# PWR_P3V3.net
KiCad netlist of a schematic drawn in Altium Designer
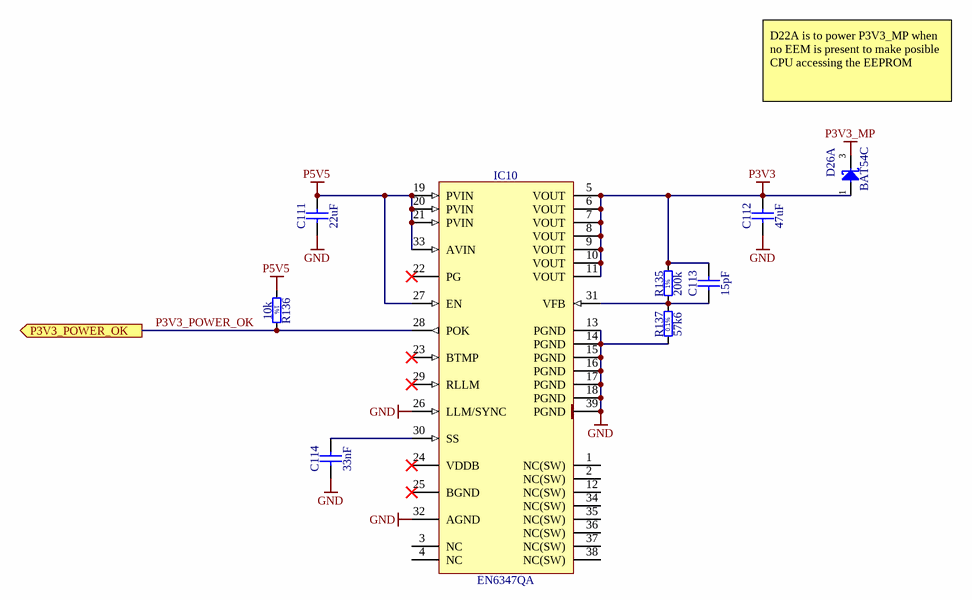
[diagram p0: PWR_P3V3.SchDoc]

(export (version "E")
  (design (tool "Eeschema 10.0.6"))
  (components
    (comp (ref "C111")
      (value "22uF")
      (footprint "CAPC2012X135N")
      (description "Non-polarised capacitor")
      (fields
        (field (name "PART NUMBER") "CC0805_22UF_16V_10%_X5R")
        (field (name "VOLTAGE") "16V")
        (field (name "AUTHOR") "CERN DEM JLC")
      )
      (libsource (lib "Capacitors") (part "Capacitor - non polarized"))
    )
    (comp (ref "C112")
      (value "47uF")
      (footprint "CAPC3216X180N")
      (description "Non-polarised capacitor")
      (fields
        (field (name "PART NUMBER") "CC1206_47UF_25V_20%_X5R")
        (field (name "VOLTAGE") "25V")
        (field (name "AUTHOR") "CERN DEM JLC")
      )
      (libsource (lib "Capacitors") (part "Capacitor - non polarized"))
    )
    (comp (ref "C113")
      (value "15pF")
      (footprint "CAPC1005X55N")
      (description "Non-polarised capacitor")
      (fields
        (field (name "PART NUMBER") "CC0402_15PF_50V_5%_C0G")
        (field (name "VOLTAGE") "50V")
        (field (name "AUTHOR") "CERN DEM JLC")
      )
      (libsource (lib "Capacitors") (part "Capacitor - non polarized"))
    )
    (comp (ref "C114")
      (value "33nF")
      (footprint "CAPC1005X55N")
      (description "Non-polarised capacitor")
      (fields
        (field (name "PART NUMBER") "CC0402_33NF_16V_10%_X7R")
        (field (name "VOLTAGE") "16V")
        (field (name "AUTHOR") "CERN DEM JLC")
      )
      (libsource (lib "Capacitors") (part "Capacitor - non polarized"))
    )
    (comp (ref "D26")
      (value "BAT54C")
      (footprint "SOT95P240X130-3N")
      (description "Dual Common Cathode Schottky Diodes")
      (fields
        (field (name "VOLTAGE") "30V")
        (field (name "POWER") "200mA")
        (field (name "AUTHOR") "CERN DEM JLC")
      )
      (libsource (lib "ICs And Semiconductors") (part "Diode Schottky x2 A1C3_A2C3"))
    )
    (comp (ref "IC10")
      (value "EN6347QA")
      (footprint "EN63xx")
      (description "4A PowerSoC Voltage Mode Synchronous PWM Buck with Integrated Inductor")
      (libsource (lib "altium-import") (part "root_0_EN6347QA_"))
    )
    (comp (ref "R135")
      (value "200k")
      (footprint "RESC1005X40N")
      (description "Resistor - 1%")
      (fields
        (field (name "PART NUMBER") "R0402_200K_1%_0.0625W_100PPM")
        (field (name "MANUFACTURER") "GENERIC")
        (field (name "AUTHOR") "CERN DEM JLC")
      )
      (libsource (lib "Resistors") (part "Resistor - 1%"))
    )
    (comp (ref "R136")
      (value "10k")
      (footprint "RESC1005X40N")
      (description "Resistor - 1%")
      (fields
        (field (name "PART NUMBER") "R0402_10K_1%_0.0625W_100PPM")
        (field (name "MANUFACTURER") "GENERIC")
        (field (name "AUTHOR") "CERN DEM JLC")
      )
      (libsource (lib "Resistors") (part "Resistor - 1%"))
    )
    (comp (ref "R137")
      (value "57k6")
      (footprint "RESC1608X55N")
      (description "Resistor - 0.1%")
      (fields
        (field (name "PART NUMBER") "R0603_57K6_0.1%_0.063W_10PPM")
        (field (name "MANUFACTURER") "GENERIC")
        (field (name "AUTHOR") "CERN DEM JLC")
      )
      (libsource (lib "Resistors") (part "Resistor - 0.1%"))
    )
  )
  (nets
    (net (code "1") (name "/P3V3_POWER_OK") (class "Default")
      (node (ref "IC10") (pin "28") (pinfunction "POK_28") (pintype "output"))
      (node (ref "R136") (pin "2") (pinfunction "2_2") (pintype "passive"))
    )
    (net (code "2") (name "GND") (class "Default")
      (node (ref "C111") (pin "1") (pinfunction "1_1") (pintype "passive"))
      (node (ref "C112") (pin "1") (pinfunction "1_1") (pintype "passive"))
      (node (ref "C114") (pin "1") (pinfunction "1_1") (pintype "passive"))
      (node (ref "IC10") (pin "13") (pinfunction "PGND_13") (pintype "power_in"))
      (node (ref "IC10") (pin "14") (pinfunction "PGND_14") (pintype "power_in"))
      (node (ref "IC10") (pin "15") (pinfunction "PGND_15") (pintype "power_in"))
      (node (ref "IC10") (pin "16") (pinfunction "PGND_16") (pintype "power_in"))
      (node (ref "IC10") (pin "17") (pinfunction "PGND_17") (pintype "power_in"))
      (node (ref "IC10") (pin "18") (pinfunction "PGND_18") (pintype "power_in"))
      (node (ref "IC10") (pin "26") (pinfunction "LLM/SYNC_26") (pintype "input"))
      (node (ref "IC10") (pin "32") (pinfunction "AGND_32") (pintype "power_in"))
      (node (ref "IC10") (pin "39") (pinfunction "PGND_39") (pintype "power_in"))
      (node (ref "R137") (pin "1") (pinfunction "1_1") (pintype "passive"))
    )
    (net (code "3") (name "Net-(IC10-SS)") (class "Default")
      (node (ref "C114") (pin "2") (pinfunction "2_2") (pintype "passive"))
      (node (ref "IC10") (pin "30") (pinfunction "SS_30") (pintype "input"))
    )
    (net (code "4") (name "Net-(IC10-VFB)") (class "Default")
      (node (ref "C113") (pin "1") (pinfunction "1_1") (pintype "passive"))
      (node (ref "IC10") (pin "31") (pinfunction "VFB_31") (pintype "input"))
      (node (ref "R135") (pin "1") (pinfunction "1_1") (pintype "passive"))
      (node (ref "R137") (pin "2") (pinfunction "2_2") (pintype "passive"))
    )
    (net (code "5") (name "P3V3") (class "Default")
      (node (ref "C112") (pin "2") (pinfunction "2_2") (pintype "passive"))
      (node (ref "C113") (pin "2") (pinfunction "2_2") (pintype "passive"))
      (node (ref "D26") (pin "1") (pinfunction "A_1") (pintype "passive"))
      (node (ref "IC10") (pin "10") (pinfunction "VOUT_10") (pintype "power_in"))
      (node (ref "IC10") (pin "11") (pinfunction "VOUT_11") (pintype "power_in"))
      (node (ref "IC10") (pin "5") (pinfunction "VOUT_5") (pintype "power_in"))
      (node (ref "IC10") (pin "6") (pinfunction "VOUT_6") (pintype "power_in"))
      (node (ref "IC10") (pin "7") (pinfunction "VOUT_7") (pintype "power_in"))
      (node (ref "IC10") (pin "8") (pinfunction "VOUT_8") (pintype "power_in"))
      (node (ref "IC10") (pin "9") (pinfunction "VOUT_9") (pintype "power_in"))
      (node (ref "R135") (pin "2") (pinfunction "2_2") (pintype "passive"))
    )
    (net (code "6") (name "P3V3_MP") (class "Default")
      (node (ref "D26") (pin "3") (pinfunction "COMC_3") (pintype "passive"))
    )
    (net (code "7") (name "P5V5") (class "Default")
      (node (ref "C111") (pin "2") (pinfunction "2_2") (pintype "passive"))
      (node (ref "IC10") (pin "19") (pinfunction "PVIN_19") (pintype "input"))
      (node (ref "IC10") (pin "20") (pinfunction "PVIN_20") (pintype "input"))
      (node (ref "IC10") (pin "21") (pinfunction "PVIN_21") (pintype "input"))
      (node (ref "IC10") (pin "27") (pinfunction "EN_27") (pintype "input"))
      (node (ref "IC10") (pin "33") (pinfunction "AVIN_33") (pintype "input"))
      (node (ref "R136") (pin "1") (pinfunction "1_1") (pintype "passive"))
    )
    (net (code "8") (name "unconnected-(IC10-BGND-Pad25)") (class "Default")
      (node (ref "IC10") (pin "25") (pinfunction "BGND_25") (pintype "power_in+no_connect"))
    )
    (net (code "9") (name "unconnected-(IC10-BTMP-Pad23)") (class "Default")
      (node (ref "IC10") (pin "23") (pinfunction "BTMP_23") (pintype "input+no_connect"))
    )
    (net (code "10") (name "unconnected-(IC10-NC(SW)-Pad1)") (class "Default")
      (node (ref "IC10") (pin "1") (pinfunction "NC(SW)_1") (pintype "passive"))
    )
    (net (code "11") (name "unconnected-(IC10-NC(SW)-Pad2)") (class "Default")
      (node (ref "IC10") (pin "2") (pinfunction "NC(SW)_2") (pintype "passive"))
    )
    (net (code "12") (name "unconnected-(IC10-NC(SW)-Pad12)") (class "Default")
      (node (ref "IC10") (pin "12") (pinfunction "NC(SW)_12") (pintype "passive"))
    )
    (net (code "13") (name "unconnected-(IC10-NC(SW)-Pad34)") (class "Default")
      (node (ref "IC10") (pin "34") (pinfunction "NC(SW)_34") (pintype "power_in"))
    )
    (net (code "14") (name "unconnected-(IC10-NC(SW)-Pad35)") (class "Default")
      (node (ref "IC10") (pin "35") (pinfunction "NC(SW)_35") (pintype "power_in"))
    )
    (net (code "15") (name "unconnected-(IC10-NC(SW)-Pad36)") (class "Default")
      (node (ref "IC10") (pin "36") (pinfunction "NC(SW)_36") (pintype "power_in"))
    )
    (net (code "16") (name "unconnected-(IC10-NC(SW)-Pad37)") (class "Default")
      (node (ref "IC10") (pin "37") (pinfunction "NC(SW)_37") (pintype "power_in"))
    )
    (net (code "17") (name "unconnected-(IC10-NC(SW)-Pad38)") (class "Default")
      (node (ref "IC10") (pin "38") (pinfunction "NC(SW)_38") (pintype "power_in"))
    )
    (net (code "18") (name "unconnected-(IC10-NC-Pad3)") (class "Default")
      (node (ref "IC10") (pin "3") (pinfunction "NC_3") (pintype "passive"))
    )
    (net (code "19") (name "unconnected-(IC10-NC-Pad4)") (class "Default")
      (node (ref "IC10") (pin "4") (pinfunction "NC_4") (pintype "passive"))
    )
    (net (code "20") (name "unconnected-(IC10-PG-Pad22)") (class "Default")
      (node (ref "IC10") (pin "22") (pinfunction "PG_22") (pintype "passive+no_connect"))
    )
    (net (code "21") (name "unconnected-(IC10-RLLM-Pad29)") (class "Default")
      (node (ref "IC10") (pin "29") (pinfunction "RLLM_29") (pintype "input+no_connect"))
    )
    (net (code "22") (name "unconnected-(IC10-VDDB-Pad24)") (class "Default")
      (node (ref "IC10") (pin "24") (pinfunction "VDDB_24") (pintype "power_in+no_connect"))
    )
  )
)
